# helloGame1_5.net
KiCad netlist of a schematic drawn in EAGLE
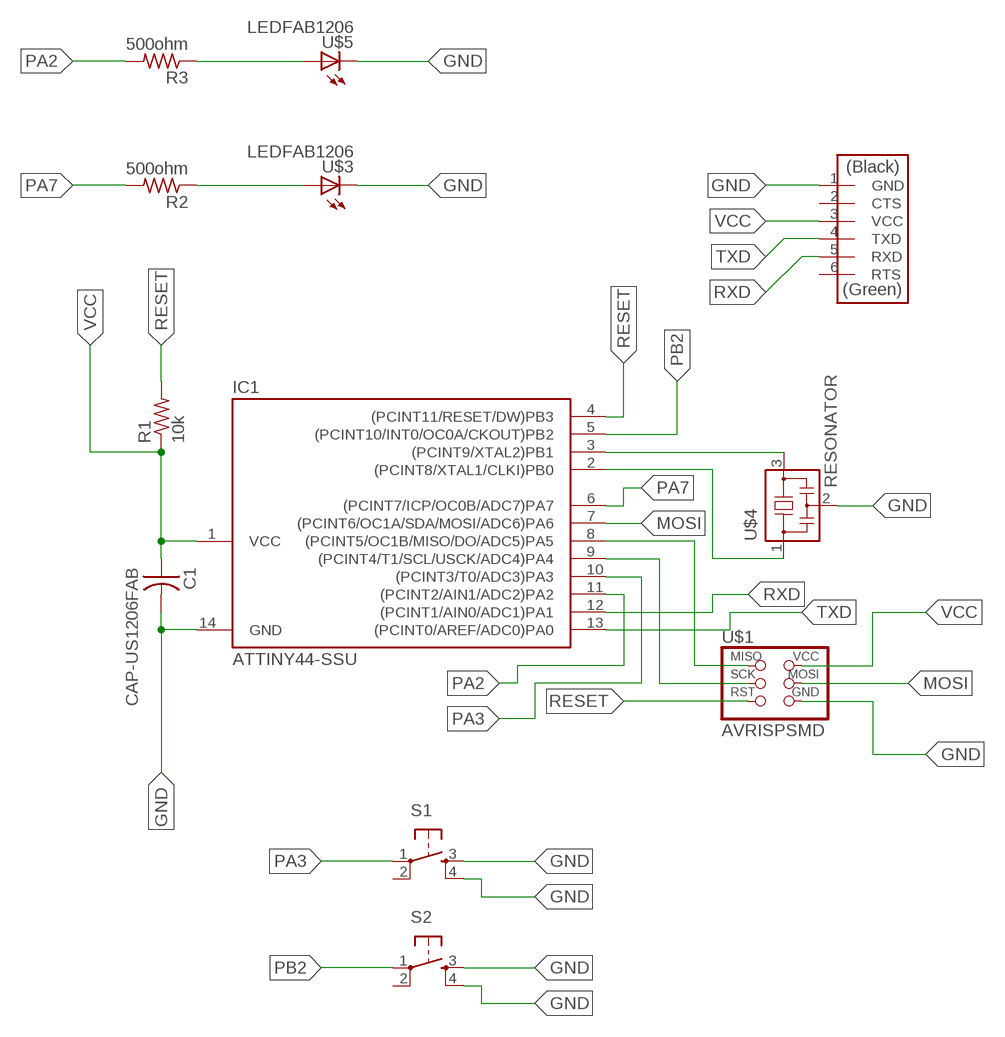
[diagram p0: schematic, sheet 1]

(export (version "E")
  (design (tool "Eeschema 10.0.6"))
  (components
    (comp (ref "C1")
      (value "CAP-US1206FAB")
      (footprint "eagle-import:C1206FAB")
      (libsource (lib "eagle-import") (part "CAP-US1206FAB"))
    )
    (comp (ref "IC1")
      (value "ATTINY44-SSU")
      (footprint "eagle-import:SOIC14")
      (libsource (lib "eagle-import") (part "ATTINY44-SSU"))
    )
    (comp (ref "R1")
      (value "10k")
      (footprint "eagle-import:R1206FAB")
      (libsource (lib "eagle-import") (part "RES-US1206FAB"))
    )
    (comp (ref "R2")
      (value "500ohm")
      (footprint "eagle-import:R1206FAB")
      (libsource (lib "eagle-import") (part "RES-US1206FAB"))
    )
    (comp (ref "R3")
      (value "500ohm")
      (footprint "eagle-import:R1206FAB")
      (libsource (lib "eagle-import") (part "RES-US1206FAB"))
    )
    (comp (ref "S1")
      (value "6MM_SWITCH6MM_SWITCH")
      (footprint "eagle-import:6MM_SWITCH")
      (libsource (lib "eagle-import") (part "6MM_SWITCH6MM_SWITCH"))
    )
    (comp (ref "S2")
      (value "6MM_SWITCH6MM_SWITCH")
      (footprint "eagle-import:6MM_SWITCH")
      (libsource (lib "eagle-import") (part "6MM_SWITCH6MM_SWITCH"))
    )
    (comp (ref "U$1")
      (value "AVRISPSMD")
      (footprint "eagle-import:2X03SMD")
      (libsource (lib "eagle-import") (part "AVRISPSMD"))
    )
    (comp (ref "U$2")
      (value "FTDI-SMD-HEADER")
      (footprint "eagle-import:1X06SMD")
      (libsource (lib "eagle-import") (part "FTDI-SMD-HEADER"))
    )
    (comp (ref "U$3")
      (value "LEDFAB1206")
      (footprint "eagle-import:LED1206FAB")
      (libsource (lib "eagle-import") (part "LEDFAB1206"))
    )
    (comp (ref "U$4")
      (value "RESONATOR")
      (footprint "eagle-import:EFOBM")
      (libsource (lib "eagle-import") (part "RESONATOR"))
    )
    (comp (ref "U$5")
      (value "LEDFAB1206")
      (footprint "eagle-import:LED1206FAB")
      (libsource (lib "eagle-import") (part "LEDFAB1206"))
    )
  )
  (nets
    (net (code "1") (name "GND") (class "Default")
      (node (ref "C1") (pin "2") (pinfunction "2_2") (pintype "passive"))
      (node (ref "IC1") (pin "14") (pinfunction "GND_14") (pintype "power_in"))
      (node (ref "S1") (pin "3") (pinfunction "S_3") (pintype "passive"))
      (node (ref "S1") (pin "4") (pinfunction "S1_4") (pintype "passive"))
      (node (ref "S2") (pin "3") (pinfunction "S_3") (pintype "passive"))
      (node (ref "S2") (pin "4") (pinfunction "S1_4") (pintype "passive"))
      (node (ref "U$1") (pin "6") (pinfunction "GND_6") (pintype "passive"))
      (node (ref "U$2") (pin "1") (pinfunction "GND_1") (pintype "bidirectional"))
      (node (ref "U$3") (pin "2") (pinfunction "C_2") (pintype "passive"))
      (node (ref "U$4") (pin "2") (pinfunction "2_2") (pintype "passive"))
      (node (ref "U$5") (pin "2") (pinfunction "C_2") (pintype "passive"))
    )
    (net (code "2") (name "MOSI") (class "Default")
      (node (ref "IC1") (pin "7") (pinfunction "(PCINT6/OC1A/SDA/MOSI/ADC6)PA6_7") (pintype "bidirectional"))
      (node (ref "U$1") (pin "4") (pinfunction "MOSI_4") (pintype "passive"))
    )
    (net (code "3") (name "Net-(IC1-(PCINT4{slash}T1{slash}SCL{slash}USCK{slash}ADC4)PA4)") (class "Default")
      (node (ref "IC1") (pin "9") (pinfunction "(PCINT4/T1/SCL/USCK/ADC4)PA4_9") (pintype "bidirectional"))
      (node (ref "U$1") (pin "3") (pinfunction "SCK_3") (pintype "passive"))
    )
    (net (code "4") (name "Net-(IC1-(PCINT5{slash}OC1B{slash}MISO{slash}DO{slash}ADC5)PA5)") (class "Default")
      (node (ref "IC1") (pin "8") (pinfunction "(PCINT5/OC1B/MISO/DO/ADC5)PA5_8") (pintype "bidirectional"))
      (node (ref "U$1") (pin "1") (pinfunction "MISO_1") (pintype "passive"))
    )
    (net (code "5") (name "Net-(IC1-(PCINT8{slash}XTAL1{slash}CLKI)PB0)") (class "Default")
      (node (ref "IC1") (pin "2") (pinfunction "(PCINT8/XTAL1/CLKI)PB0_2") (pintype "bidirectional"))
      (node (ref "U$4") (pin "1") (pinfunction "1_1") (pintype "passive"))
    )
    (net (code "6") (name "Net-(IC1-(PCINT9{slash}XTAL2)PB1)") (class "Default")
      (node (ref "IC1") (pin "3") (pinfunction "(PCINT9/XTAL2)PB1_3") (pintype "bidirectional"))
      (node (ref "U$4") (pin "3") (pinfunction "3_3") (pintype "passive"))
    )
    (net (code "7") (name "Net-(U$3-A)") (class "Default")
      (node (ref "R2") (pin "1") (pinfunction "1_1") (pintype "passive"))
      (node (ref "U$3") (pin "1") (pinfunction "A_1") (pintype "passive"))
    )
    (net (code "8") (name "Net-(U$5-A)") (class "Default")
      (node (ref "R3") (pin "1") (pinfunction "1_1") (pintype "passive"))
      (node (ref "U$5") (pin "1") (pinfunction "A_1") (pintype "passive"))
    )
    (net (code "9") (name "PA2") (class "Default")
      (node (ref "IC1") (pin "11") (pinfunction "(PCINT2/AIN1/ADC2)PA2_11") (pintype "bidirectional"))
      (node (ref "R3") (pin "2") (pinfunction "2_2") (pintype "passive"))
    )
    (net (code "10") (name "PA3") (class "Default")
      (node (ref "IC1") (pin "10") (pinfunction "(PCINT3/T0/ADC3)PA3_10") (pintype "bidirectional"))
      (node (ref "S1") (pin "1") (pinfunction "P_1") (pintype "passive"))
    )
    (net (code "11") (name "PA7") (class "Default")
      (node (ref "IC1") (pin "6") (pinfunction "(PCINT7/ICP/OC0B/ADC7)PA7_6") (pintype "bidirectional"))
      (node (ref "R2") (pin "2") (pinfunction "2_2") (pintype "passive"))
    )
    (net (code "12") (name "PB2") (class "Default")
      (node (ref "IC1") (pin "5") (pinfunction "(PCINT10/INT0/OC0A/CKOUT)PB2_5") (pintype "bidirectional"))
      (node (ref "S2") (pin "1") (pinfunction "P_1") (pintype "passive"))
    )
    (net (code "13") (name "RESET") (class "Default")
      (node (ref "IC1") (pin "4") (pinfunction "(PCINT11/RESET/DW)PB3_4") (pintype "bidirectional"))
      (node (ref "R1") (pin "2") (pinfunction "2_2") (pintype "passive"))
      (node (ref "U$1") (pin "5") (pinfunction "RST_5") (pintype "passive"))
    )
    (net (code "14") (name "RXD") (class "Default")
      (node (ref "IC1") (pin "12") (pinfunction "(PCINT1/AIN0/ADC1)PA1_12") (pintype "bidirectional"))
      (node (ref "U$2") (pin "5") (pinfunction "RXD_5") (pintype "bidirectional"))
    )
    (net (code "15") (name "TXD") (class "Default")
      (node (ref "IC1") (pin "13") (pinfunction "(PCINT0/AREF/ADC0)PA0_13") (pintype "bidirectional"))
      (node (ref "U$2") (pin "4") (pinfunction "TXD_4") (pintype "bidirectional"))
    )
    (net (code "16") (name "VCC") (class "Default")
      (node (ref "C1") (pin "1") (pinfunction "1_1") (pintype "passive"))
      (node (ref "IC1") (pin "1") (pinfunction "VCC_1") (pintype "power_in"))
      (node (ref "R1") (pin "1") (pinfunction "1_1") (pintype "passive"))
      (node (ref "U$1") (pin "2") (pinfunction "VCC_2") (pintype "passive"))
      (node (ref "U$2") (pin "3") (pinfunction "VCC_3") (pintype "bidirectional"))
    )
    (net (code "17") (name "unconnected-(S1-P1-Pad2)") (class "Default")
      (node (ref "S1") (pin "2") (pinfunction "P1_2") (pintype "passive"))
    )
    (net (code "18") (name "unconnected-(S2-P1-Pad2)") (class "Default")
      (node (ref "S2") (pin "2") (pinfunction "P1_2") (pintype "passive"))
    )
    (net (code "19") (name "unconnected-(U$2-CTS-Pad2)") (class "Default")
      (node (ref "U$2") (pin "2") (pinfunction "CTS_2") (pintype "bidirectional"))
    )
    (net (code "20") (name "unconnected-(U$2-RTS-Pad6)") (class "Default")
      (node (ref "U$2") (pin "6") (pinfunction "RTS_6") (pintype "bidirectional"))
    )
  )
)
